# M2_Power.net
KiCad netlist of a schematic drawn in Altium Designer
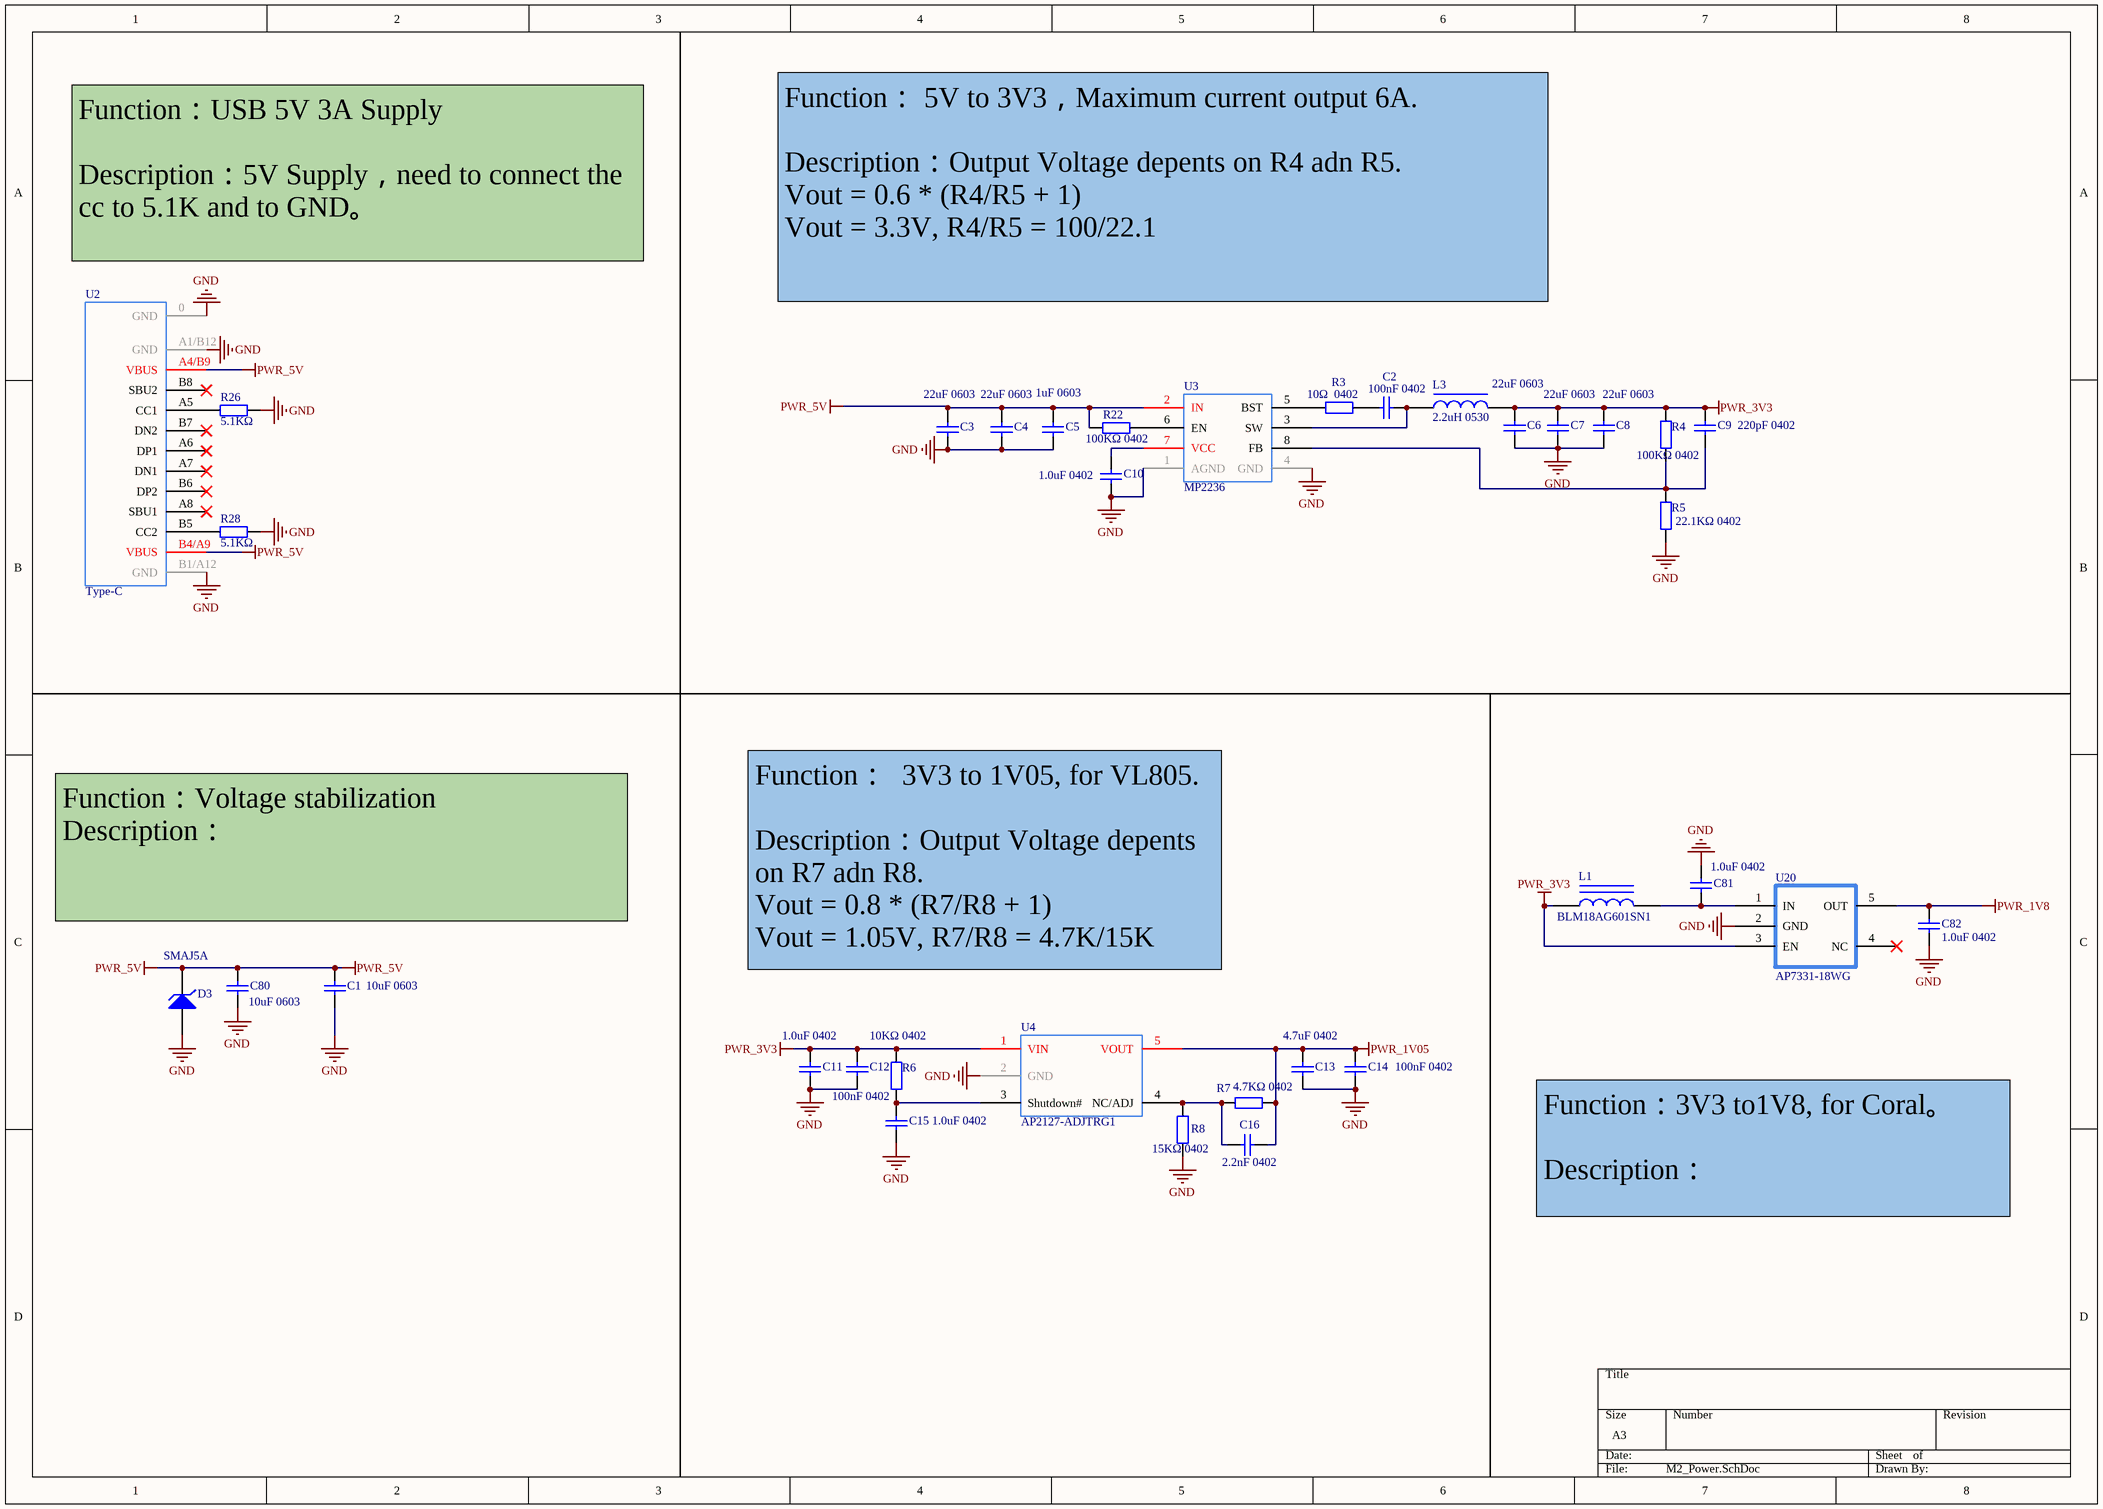
[diagram p0: M2_Power.SchDoc]

(export (version "E")
  (design (tool "Eeschema 10.0.6"))
  (components
    (comp (ref "C1")
      (value "10uF 0603")
      (footprint "0603_C")
      (description "贴片电容")
      (libsource (lib "Miscellaneous Devices LC") (part "0603 10uF (106) 10% 10V"))
    )
    (comp (ref "C2")
      (value "100nF 0402")
      (footprint "0402_C")
      (description "贴片电容")
      (libsource (lib "Miscellaneous Devices LC") (part "0402 100nF (104) 10% 16V"))
    )
    (comp (ref "C3")
      (value "22uF 0603")
      (footprint "0603_C")
      (description "贴片电容")
      (libsource (lib "Miscellaneous Devices LC") (part "0603 22uF (226) 20% 6.3V"))
    )
    (comp (ref "C4")
      (value "22uF 0603")
      (footprint "0603_C")
      (description "贴片电容")
      (libsource (lib "Miscellaneous Devices LC") (part "0603 22uF (226) 20% 6.3V"))
    )
    (comp (ref "C5")
      (value "1uF 0603")
      (footprint "0603_C")
      (description "贴片电容")
      (libsource (lib "Miscellaneous Devices LC") (part "0603 1uF (105) 10% 50V"))
    )
    (comp (ref "C6")
      (value "22uF 0603")
      (footprint "0603_C")
      (description "贴片电容")
      (libsource (lib "Miscellaneous Devices LC") (part "0603 22uF (226) 20% 6.3V"))
    )
    (comp (ref "C7")
      (value "22uF 0603")
      (footprint "0603_C")
      (description "贴片电容")
      (libsource (lib "Miscellaneous Devices LC") (part "0603 22uF (226) 20% 6.3V"))
    )
    (comp (ref "C8")
      (value "22uF 0603")
      (footprint "0603_C")
      (description "贴片电容")
      (libsource (lib "Miscellaneous Devices LC") (part "0603 22uF (226) 20% 6.3V"))
    )
    (comp (ref "C9")
      (value "220pF 0402")
      (footprint "0402_C")
      (description "贴片电容")
      (libsource (lib "Miscellaneous Devices LC") (part "0402 220pF (221) 10% 50V"))
    )
    (comp (ref "C10")
      (value "1.0uF 0402")
      (footprint "0402_C")
      (description "贴片电容")
      (libsource (lib "Miscellaneous Devices LC") (part "0402 1.0uF (105) 10% 25V"))
    )
    (comp (ref "C11")
      (value "1.0uF 0402")
      (footprint "0402_C")
      (description "贴片电容")
      (libsource (lib "Miscellaneous Devices LC") (part "0402 1.0uF (105) 10% 25V"))
    )
    (comp (ref "C12")
      (value "100nF 0402")
      (footprint "0402_C")
      (description "贴片电容")
      (libsource (lib "Miscellaneous Devices LC") (part "0402 100nF (104) 10% 16V"))
    )
    (comp (ref "C13")
      (value "4.7uF 0402")
      (footprint "0402_C")
      (description "贴片电容")
      (libsource (lib "Miscellaneous Devices LC") (part "0402 4.7uF (475) 20% 10V"))
    )
    (comp (ref "C14")
      (value "100nF 0402")
      (footprint "0402_C")
      (description "贴片电容")
      (libsource (lib "Miscellaneous Devices LC") (part "0402 100nF (104) 10% 16V"))
    )
    (comp (ref "C15")
      (value "1.0uF 0402")
      (footprint "0402_C")
      (description "贴片电容")
      (libsource (lib "Miscellaneous Devices LC") (part "0402 1.0uF (105) 10% 25V"))
    )
    (comp (ref "C16")
      (value "2.2nF 0402")
      (footprint "0402_C")
      (description "贴片电容")
      (libsource (lib "Miscellaneous Devices LC") (part "0402 2.2nF (222) 10% 50V"))
    )
    (comp (ref "C80")
      (value "10uF 0603")
      (footprint "0603_C")
      (description "贴片电容")
      (libsource (lib "Miscellaneous Devices LC") (part "0603 10uF (106) 10% 10V"))
    )
    (comp (ref "C81")
      (value "1.0uF 0402")
      (footprint "0402_C")
      (description "贴片电容")
      (libsource (lib "Miscellaneous Devices LC") (part "0402 1.0uF (105) 10% 25V"))
    )
    (comp (ref "C82")
      (value "1.0uF 0402")
      (footprint "0402_C")
      (description "贴片电容")
      (libsource (lib "Miscellaneous Devices LC") (part "0402 1.0uF (105) 10% 25V"))
    )
    (comp (ref "D3")
      (value "SMAJ5A")
      (footprint "SMAJ5A")
      (description "TVS")
      (libsource (lib "Mars") (part "SMAJ5A"))
    )
    (comp (ref "L1")
      (value "BLM18AG601SN1")
      (footprint "0603_L")
      (description "贴片电感")
      (libsource (lib "Miscellaneous Devices LC") (part "0603 10uH 10%"))
    )
    (comp (ref "L3")
      (value "2.2uH 0530")
      (footprint "0530")
      (description "2.2uH 0630")
      (libsource (lib "Mars") (part "2.2uH"))
    )
    (comp (ref "R3")
      (value "10Ω  0402")
      (footprint "0402_R")
      (description "贴片电阻")
      (libsource (lib "Miscellaneous Devices LC") (part "0402 10Ω (10R0) 1%"))
    )
    (comp (ref "R4")
      (value "100KΩ 0402")
      (footprint "0402_R")
      (description "贴片电阻")
      (libsource (lib "") (part "0402 100KΩ (1003) 1%_1"))
    )
    (comp (ref "R5")
      (value "22.1KΩ 0402")
      (footprint "0402_R")
      (description "贴片电阻")
      (libsource (lib "Miscellaneous Devices LC") (part "0402 10KΩ (1002) 1%"))
    )
    (comp (ref "R6")
      (value "10KΩ 0402")
      (footprint "0402_R")
      (description "贴片电阻")
      (libsource (lib "Miscellaneous Devices LC") (part "0402 10KΩ (1002) 1%"))
    )
    (comp (ref "R7")
      (value "4.7KΩ 0402")
      (footprint "0402_R")
      (description "贴片电阻")
      (libsource (lib "Miscellaneous Devices LC") (part "0402 4.7KΩ (4701) 1%"))
    )
    (comp (ref "R8")
      (value "15KΩ 0402")
      (footprint "0402_R")
      (description "贴片电阻")
      (libsource (lib "Miscellaneous Devices LC") (part "0402 15KΩ (1502) 1%"))
    )
    (comp (ref "R22")
      (value "100KΩ 0402")
      (footprint "0402_R")
      (description "贴片电阻")
      (libsource (lib "Miscellaneous Devices LC") (part "0402 100KΩ (1003) 1%"))
    )
    (comp (ref "R26")
      (value "5.1KΩ")
      (footprint "0402_R")
      (description "贴片电阻")
      (libsource (lib "Miscellaneous Devices LC") (part "0402 5.1KΩ (5101) 1%"))
    )
    (comp (ref "R28")
      (value "5.1KΩ")
      (footprint "0402_R")
      (description "贴片电阻")
      (libsource (lib "Miscellaneous Devices LC") (part "0402 5.1KΩ (5101) 1%"))
    )
    (comp (ref "U2")
      (value "Type-C")
      (footprint "Type-C-16P")
      (description "Type-C-16P")
      (libsource (lib "Mars") (part "Type-C-16P"))
    )
    (comp (ref "U3")
      (value "MP2236")
      (footprint "MP2236")
      (description "Vin=18, Iout=6A")
      (libsource (lib "Mars") (part "MP2236"))
    )
    (comp (ref "U4")
      (value "AP2127-ADJTRG1")
      (footprint "AP2127K")
      (description "3.3V-1.05V")
      (libsource (lib "Mars") (part "AP2127-ADJTRG1"))
    )
    (comp (ref "U20")
      (value "AP7331-18WG")
      (footprint "AP7331-18WG")
      (description "Camera 1.8V")
      (libsource (lib "Sensor") (part "AP7331-18WG"))
    )
  )
  (nets
    (net (code "1") (name "GND") (class "Default")
      (node (ref "C1") (pin "1") (pinfunction "1_1") (pintype "passive"))
      (node (ref "C10") (pin "1") (pinfunction "1_1") (pintype "passive"))
      (node (ref "C11") (pin "1") (pinfunction "1_1") (pintype "passive"))
      (node (ref "C12") (pin "1") (pinfunction "1_1") (pintype "passive"))
      (node (ref "C13") (pin "1") (pinfunction "1_1") (pintype "passive"))
      (node (ref "C14") (pin "1") (pinfunction "1_1") (pintype "passive"))
      (node (ref "C15") (pin "1") (pinfunction "1_1") (pintype "passive"))
      (node (ref "C3") (pin "1") (pinfunction "1_1") (pintype "passive"))
      (node (ref "C4") (pin "1") (pinfunction "1_1") (pintype "passive"))
      (node (ref "C5") (pin "1") (pinfunction "1_1") (pintype "passive"))
      (node (ref "C6") (pin "1") (pinfunction "1_1") (pintype "passive"))
      (node (ref "C7") (pin "1") (pinfunction "1_1") (pintype "passive"))
      (node (ref "C8") (pin "1") (pinfunction "1_1") (pintype "passive"))
      (node (ref "C80") (pin "1") (pinfunction "1_1") (pintype "passive"))
      (node (ref "C81") (pin "1") (pinfunction "1_1") (pintype "passive"))
      (node (ref "C82") (pin "1") (pinfunction "1_1") (pintype "passive"))
      (node (ref "D3") (pin "1") (pinfunction "A_1") (pintype "passive"))
      (node (ref "R26") (pin "2") (pinfunction "2_2") (pintype "passive"))
      (node (ref "R28") (pin "2") (pinfunction "2_2") (pintype "passive"))
      (node (ref "R5") (pin "1") (pinfunction "1_1") (pintype "passive"))
      (node (ref "R8") (pin "1") (pinfunction "1_1") (pintype "passive"))
      (node (ref "U2") (pin "0") (pinfunction "GND_0") (pintype "passive"))
      (node (ref "U2") (pin "A1/B12") (pinfunction "GND_A1/B12") (pintype "passive"))
      (node (ref "U2") (pin "B1/A12") (pinfunction "GND_B1/A12") (pintype "passive"))
      (node (ref "U20") (pin "2") (pinfunction "GND_2") (pintype "passive"))
      (node (ref "U3") (pin "1") (pinfunction "AGND_1") (pintype "passive"))
      (node (ref "U3") (pin "4") (pinfunction "GND_4") (pintype "passive"))
      (node (ref "U4") (pin "2") (pinfunction "GND_2") (pintype "passive"))
    )
    (net (code "2") (name "Net-(C2-Pad1)") (class "Default")
      (node (ref "C2") (pin "1") (pinfunction "1_1") (pintype "passive"))
      (node (ref "R3") (pin "2") (pinfunction "2_2") (pintype "passive"))
    )
    (net (code "3") (name "Net-(U2-CC1)") (class "Default")
      (node (ref "R26") (pin "1") (pinfunction "1_1") (pintype "passive"))
      (node (ref "U2") (pin "A5") (pinfunction "CC1_A5") (pintype "passive"))
    )
    (net (code "4") (name "Net-(U2-CC2)") (class "Default")
      (node (ref "R28") (pin "1") (pinfunction "1_1") (pintype "passive"))
      (node (ref "U2") (pin "B5") (pinfunction "CC2_B5") (pintype "passive"))
    )
    (net (code "5") (name "Net-(U3-BST)") (class "Default")
      (node (ref "R3") (pin "1") (pinfunction "1_1") (pintype "passive"))
      (node (ref "U3") (pin "5") (pinfunction "BST_5") (pintype "passive"))
    )
    (net (code "6") (name "Net-(U3-EN)") (class "Default")
      (node (ref "R22") (pin "2") (pinfunction "2_2") (pintype "passive"))
      (node (ref "U3") (pin "6") (pinfunction "EN_6") (pintype "passive"))
    )
    (net (code "7") (name "Net-(U3-FB)") (class "Default")
      (node (ref "C9") (pin "1") (pinfunction "1_1") (pintype "passive"))
      (node (ref "R4") (pin "1") (pinfunction "1_1") (pintype "passive"))
      (node (ref "R5") (pin "2") (pinfunction "2_2") (pintype "passive"))
      (node (ref "U3") (pin "8") (pinfunction "FB_8") (pintype "passive"))
    )
    (net (code "8") (name "Net-(U3-SW)") (class "Default")
      (node (ref "C2") (pin "2") (pinfunction "2_2") (pintype "passive"))
      (node (ref "L3") (pin "1") (pinfunction "1_1") (pintype "passive"))
      (node (ref "U3") (pin "3") (pinfunction "SW_3") (pintype "passive"))
    )
    (net (code "9") (name "Net-(U3-VCC)") (class "Default")
      (node (ref "C10") (pin "2") (pinfunction "2_2") (pintype "passive"))
      (node (ref "U3") (pin "7") (pinfunction "VCC_7") (pintype "passive"))
    )
    (net (code "10") (name "Net-(U4-NC{slash}ADJ)") (class "Default")
      (node (ref "C16") (pin "1") (pinfunction "1_1") (pintype "passive"))
      (node (ref "R7") (pin "1") (pinfunction "1_1") (pintype "passive"))
      (node (ref "R8") (pin "2") (pinfunction "2_2") (pintype "passive"))
      (node (ref "U4") (pin "4") (pinfunction "NC/ADJ_4") (pintype "passive"))
    )
    (net (code "11") (name "Net-(U4-Shutdown#)") (class "Default")
      (node (ref "C15") (pin "2") (pinfunction "2_2") (pintype "passive"))
      (node (ref "R6") (pin "1") (pinfunction "1_1") (pintype "passive"))
      (node (ref "U4") (pin "3") (pinfunction "Shutdown#_3") (pintype "passive"))
    )
    (net (code "12") (name "Net-(U20-IN)") (class "Default")
      (node (ref "C81") (pin "2") (pinfunction "2_2") (pintype "passive"))
      (node (ref "L1") (pin "2") (pinfunction "2_2") (pintype "passive"))
      (node (ref "U20") (pin "1") (pinfunction "IN_1") (pintype "passive"))
    )
    (net (code "13") (name "PWR_1V05") (class "Default")
      (node (ref "C13") (pin "2") (pinfunction "2_2") (pintype "passive"))
      (node (ref "C14") (pin "2") (pinfunction "2_2") (pintype "passive"))
      (node (ref "C16") (pin "2") (pinfunction "2_2") (pintype "passive"))
      (node (ref "R7") (pin "2") (pinfunction "2_2") (pintype "passive"))
      (node (ref "U4") (pin "5") (pinfunction "VOUT_5") (pintype "passive"))
    )
    (net (code "14") (name "PWR_1V8") (class "Default")
      (node (ref "C82") (pin "2") (pinfunction "2_2") (pintype "passive"))
      (node (ref "U20") (pin "5") (pinfunction "OUT_5") (pintype "passive"))
    )
    (net (code "15") (name "PWR_3V3") (class "Default")
      (node (ref "C11") (pin "2") (pinfunction "2_2") (pintype "passive"))
      (node (ref "C12") (pin "2") (pinfunction "2_2") (pintype "passive"))
      (node (ref "C6") (pin "2") (pinfunction "2_2") (pintype "passive"))
      (node (ref "C7") (pin "2") (pinfunction "2_2") (pintype "passive"))
      (node (ref "C8") (pin "2") (pinfunction "2_2") (pintype "passive"))
      (node (ref "C9") (pin "2") (pinfunction "2_2") (pintype "passive"))
      (node (ref "L1") (pin "1") (pinfunction "1_1") (pintype "passive"))
      (node (ref "L3") (pin "2") (pinfunction "2_2") (pintype "passive"))
      (node (ref "R4") (pin "2") (pinfunction "2_2") (pintype "passive"))
      (node (ref "R6") (pin "2") (pinfunction "2_2") (pintype "passive"))
      (node (ref "U20") (pin "3") (pinfunction "EN_3") (pintype "passive"))
      (node (ref "U4") (pin "1") (pinfunction "VIN_1") (pintype "passive"))
    )
    (net (code "16") (name "PWR_5V") (class "Default")
      (node (ref "C1") (pin "2") (pinfunction "2_2") (pintype "passive"))
      (node (ref "C3") (pin "2") (pinfunction "2_2") (pintype "passive"))
      (node (ref "C4") (pin "2") (pinfunction "2_2") (pintype "passive"))
      (node (ref "C5") (pin "2") (pinfunction "2_2") (pintype "passive"))
      (node (ref "C80") (pin "2") (pinfunction "2_2") (pintype "passive"))
      (node (ref "D3") (pin "2") (pinfunction "C_2") (pintype "passive"))
      (node (ref "R22") (pin "1") (pinfunction "1_1") (pintype "passive"))
      (node (ref "U2") (pin "A4/B9") (pinfunction "VBUS_A4/B9") (pintype "passive"))
      (node (ref "U2") (pin "B4/A9") (pinfunction "VBUS_B4/A9") (pintype "passive"))
      (node (ref "U3") (pin "2") (pinfunction "IN_2") (pintype "passive"))
    )
    (net (code "17") (name "unconnected-(U2-DN1-PadA7)") (class "Default")
      (node (ref "U2") (pin "A7") (pinfunction "DN1_A7") (pintype "passive+no_connect"))
    )
    (net (code "18") (name "unconnected-(U2-DN2-PadB7)") (class "Default")
      (node (ref "U2") (pin "B7") (pinfunction "DN2_B7") (pintype "passive+no_connect"))
    )
    (net (code "19") (name "unconnected-(U2-DP1-PadA6)") (class "Default")
      (node (ref "U2") (pin "A6") (pinfunction "DP1_A6") (pintype "passive+no_connect"))
    )
    (net (code "20") (name "unconnected-(U2-DP2-PadB6)") (class "Default")
      (node (ref "U2") (pin "B6") (pinfunction "DP2_B6") (pintype "passive+no_connect"))
    )
    (net (code "21") (name "unconnected-(U2-SBU1-PadA8)") (class "Default")
      (node (ref "U2") (pin "A8") (pinfunction "SBU1_A8") (pintype "passive+no_connect"))
    )
    (net (code "22") (name "unconnected-(U2-SBU2-PadB8)") (class "Default")
      (node (ref "U2") (pin "B8") (pinfunction "SBU2_B8") (pintype "passive+no_connect"))
    )
    (net (code "23") (name "unconnected-(U20-NC-Pad4)") (class "Default")
      (node (ref "U20") (pin "4") (pinfunction "NC_4") (pintype "power_in+no_connect"))
    )
  )
)
